# Circuit-Schematic.net
KiCad netlist of a schematic drawn in EAGLE
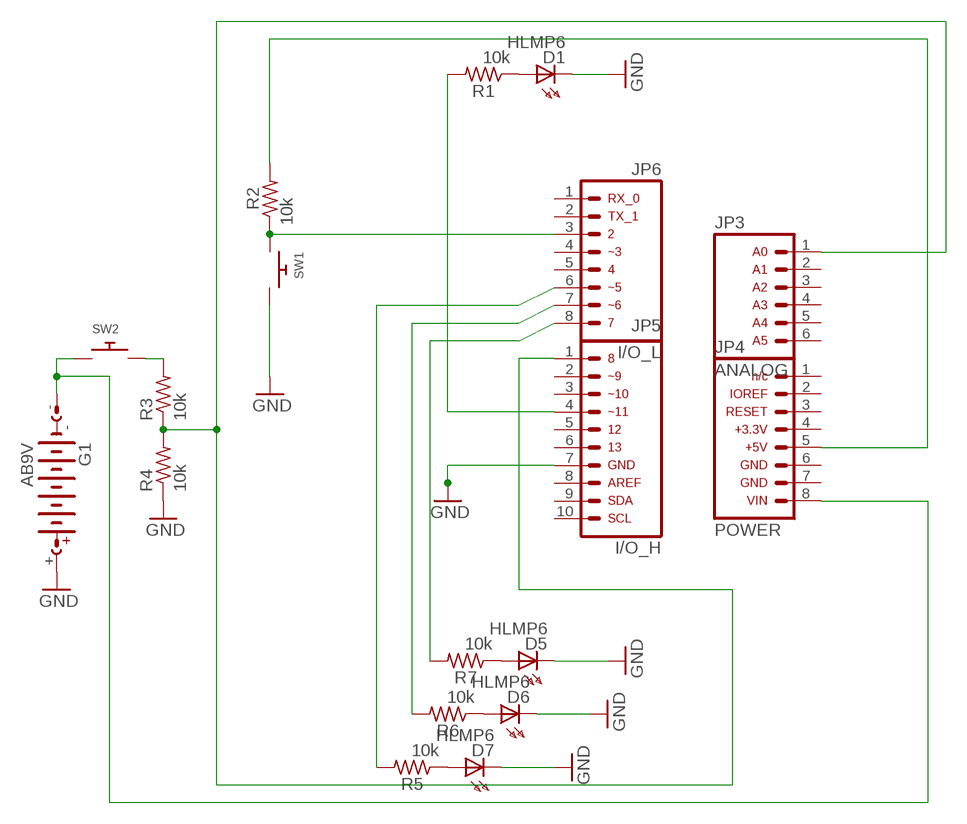
[diagram p0: schematic, sheet 1]

(export (version "E")
  (design (tool "Eeschema 10.0.6"))
  (components
    (comp (ref "D1")
      (value "HLMP6")
      (footprint "eagle-import:HLMP6")
      (fields (field (name "MF") "AGILENT TECHNOLOGIES") (field (name "MPN") "HLMP-6500"))
      (libsource (lib "eagle-import") (part "HLMP6"))
    )
    (comp (ref "D5")
      (value "HLMP6")
      (footprint "eagle-import:HLMP6")
      (fields (field (name "MF") "AGILENT TECHNOLOGIES") (field (name "MPN") "HLMP-6500"))
      (libsource (lib "eagle-import") (part "HLMP6"))
    )
    (comp (ref "D6")
      (value "HLMP6")
      (footprint "eagle-import:HLMP6")
      (fields (field (name "MF") "AGILENT TECHNOLOGIES") (field (name "MPN") "HLMP-6500"))
      (libsource (lib "eagle-import") (part "HLMP6"))
    )
    (comp (ref "D7")
      (value "HLMP6")
      (footprint "eagle-import:HLMP6")
      (fields (field (name "MF") "AGILENT TECHNOLOGIES") (field (name "MPN") "HLMP-6500"))
      (libsource (lib "eagle-import") (part "HLMP6"))
    )
    (comp (ref "G1")
      (value "AB9V")
      (footprint "eagle-import:AB9V")
      (libsource (lib "eagle-import") (part "AB9V"))
    )
    (comp (ref "JP3")
      (value "ARDUINO_CONN-ANALOGSIP")
      (footprint "eagle-import:CONN-1X06")
      (libsource (lib "eagle-import") (part "ARDUINO_CONN-ANALOGSIP"))
    )
    (comp (ref "JP4")
      (value "ARDUINO_CONN-POWERSIP")
      (footprint "eagle-import:CONN-1X08")
      (libsource (lib "eagle-import") (part "ARDUINO_CONN-POWERSIP"))
    )
    (comp (ref "JP5")
      (value "ARDUINO_CONN-IO_HSIP")
      (footprint "eagle-import:CONN-1X10")
      (libsource (lib "eagle-import") (part "ARDUINO_CONN-IO_HSIP"))
    )
    (comp (ref "JP6")
      (value "ARDUINO_CONN-IO_LSIP")
      (footprint "eagle-import:CONN-1X08")
      (libsource (lib "eagle-import") (part "ARDUINO_CONN-IO_LSIP"))
    )
    (comp (ref "R1")
      (value "10k")
      (footprint "eagle-import:R0805")
      (libsource (lib "eagle-import") (part "R-US_R0805"))
    )
    (comp (ref "R2")
      (value "10k")
      (footprint "eagle-import:R0805")
      (libsource (lib "eagle-import") (part "R-US_R0805"))
    )
    (comp (ref "R3")
      (value "10k")
      (footprint "eagle-import:R0805")
      (libsource (lib "eagle-import") (part "R-US_R0805"))
    )
    (comp (ref "R4")
      (value "10k")
      (footprint "eagle-import:R0805")
      (libsource (lib "eagle-import") (part "R-US_R0805"))
    )
    (comp (ref "R5")
      (value "10k")
      (footprint "eagle-import:R0805")
      (libsource (lib "eagle-import") (part "R-US_R0805"))
    )
    (comp (ref "R6")
      (value "10k")
      (footprint "eagle-import:R0805")
      (libsource (lib "eagle-import") (part "R-US_R0805"))
    )
    (comp (ref "R7")
      (value "10k")
      (footprint "eagle-import:R0805")
      (libsource (lib "eagle-import") (part "R-US_R0805"))
    )
    (comp (ref "SW1")
      (value "SWITCH_PUSHBUTTONSOFTTOUCHSMD_SJ")
      (footprint "eagle-import:PUSHBUTTON_SMD_SJ")
      (libsource (lib "eagle-import") (part "SWITCH_PUSHBUTTONSOFTTOUCHSMD_SJ"))
    )
    (comp (ref "SW2")
      (value "SWITCH_PUSHBUTTONSOFTTOUCHSMD_SJ")
      (footprint "eagle-import:PUSHBUTTON_SMD_SJ")
      (libsource (lib "eagle-import") (part "SWITCH_PUSHBUTTONSOFTTOUCHSMD_SJ"))
    )
  )
  (nets
    (net (code "1") (name "GND") (class "Default")
      (node (ref "D1") (pin "K") (pinfunction "K_K") (pintype "passive"))
      (node (ref "D5") (pin "K") (pinfunction "K_K") (pintype "passive"))
      (node (ref "D6") (pin "K") (pinfunction "K_K") (pintype "passive"))
      (node (ref "D7") (pin "K") (pinfunction "K_K") (pintype "passive"))
      (node (ref "G1") (pin "+") (pinfunction "+_+") (pintype "passive"))
      (node (ref "JP5") (pin "7") (pinfunction "7_7") (pintype "passive"))
      (node (ref "R4") (pin "1") (pinfunction "1_1") (pintype "passive"))
      (node (ref "SW1") (pin "P$2") (pinfunction "P$2_P$2") (pintype "passive"))
    )
    (net (code "2") (name "Net-(D1-PadA)") (class "Default")
      (node (ref "D1") (pin "A") (pinfunction "A_A") (pintype "passive"))
      (node (ref "R1") (pin "1") (pinfunction "1_1") (pintype "passive"))
    )
    (net (code "3") (name "Net-(D5-PadA)") (class "Default")
      (node (ref "D5") (pin "A") (pinfunction "A_A") (pintype "passive"))
      (node (ref "R7") (pin "1") (pinfunction "1_1") (pintype "passive"))
    )
    (net (code "4") (name "Net-(D6-PadA)") (class "Default")
      (node (ref "D6") (pin "A") (pinfunction "A_A") (pintype "passive"))
      (node (ref "R6") (pin "1") (pinfunction "1_1") (pintype "passive"))
    )
    (net (code "5") (name "Net-(D7-PadA)") (class "Default")
      (node (ref "D7") (pin "A") (pinfunction "A_A") (pintype "passive"))
      (node (ref "R5") (pin "1") (pinfunction "1_1") (pintype "passive"))
    )
    (net (code "6") (name "Net-(G1-Pad-)") (class "Default")
      (node (ref "G1") (pin "-") (pinfunction "-_-") (pintype "passive"))
      (node (ref "JP4") (pin "8") (pinfunction "8_8") (pintype "passive"))
      (node (ref "SW2") (pin "P$1") (pinfunction "P$1_P$1") (pintype "passive"))
    )
    (net (code "7") (name "Net-(JP3-Pad1)") (class "Default")
      (node (ref "JP3") (pin "1") (pinfunction "1_1") (pintype "passive"))
      (node (ref "JP5") (pin "1") (pinfunction "1_1") (pintype "passive"))
      (node (ref "R3") (pin "1") (pinfunction "1_1") (pintype "passive"))
      (node (ref "R4") (pin "2") (pinfunction "2_2") (pintype "passive"))
    )
    (net (code "8") (name "Net-(JP4-Pad5)") (class "Default")
      (node (ref "JP4") (pin "5") (pinfunction "5_5") (pintype "passive"))
      (node (ref "R2") (pin "2") (pinfunction "2_2") (pintype "passive"))
    )
    (net (code "9") (name "Net-(JP5-Pad4)") (class "Default")
      (node (ref "JP5") (pin "4") (pinfunction "4_4") (pintype "passive"))
      (node (ref "R1") (pin "2") (pinfunction "2_2") (pintype "passive"))
    )
    (net (code "10") (name "Net-(JP6-Pad3)") (class "Default")
      (node (ref "JP6") (pin "3") (pinfunction "3_3") (pintype "passive"))
      (node (ref "R2") (pin "1") (pinfunction "1_1") (pintype "passive"))
      (node (ref "SW1") (pin "P$1") (pinfunction "P$1_P$1") (pintype "passive"))
    )
    (net (code "11") (name "Net-(JP6-Pad6)") (class "Default")
      (node (ref "JP6") (pin "6") (pinfunction "6_6") (pintype "passive"))
      (node (ref "R5") (pin "2") (pinfunction "2_2") (pintype "passive"))
    )
    (net (code "12") (name "Net-(JP6-Pad7)") (class "Default")
      (node (ref "JP6") (pin "7") (pinfunction "7_7") (pintype "passive"))
      (node (ref "R6") (pin "2") (pinfunction "2_2") (pintype "passive"))
    )
    (net (code "13") (name "Net-(JP6-Pad8)") (class "Default")
      (node (ref "JP6") (pin "8") (pinfunction "8_8") (pintype "passive"))
      (node (ref "R7") (pin "2") (pinfunction "2_2") (pintype "passive"))
    )
    (net (code "14") (name "Net-(R3-Pad2)") (class "Default")
      (node (ref "R3") (pin "2") (pinfunction "2_2") (pintype "passive"))
      (node (ref "SW2") (pin "P$2") (pinfunction "P$2_P$2") (pintype "passive"))
    )
    (net (code "15") (name "unconnected-(JP3-Pad2)") (class "Default")
      (node (ref "JP3") (pin "2") (pinfunction "2_2") (pintype "passive"))
    )
    (net (code "16") (name "unconnected-(JP3-Pad3)") (class "Default")
      (node (ref "JP3") (pin "3") (pinfunction "3_3") (pintype "passive"))
    )
    (net (code "17") (name "unconnected-(JP3-Pad4)") (class "Default")
      (node (ref "JP3") (pin "4") (pinfunction "4_4") (pintype "passive"))
    )
    (net (code "18") (name "unconnected-(JP3-Pad5)") (class "Default")
      (node (ref "JP3") (pin "5") (pinfunction "5_5") (pintype "passive"))
    )
    (net (code "19") (name "unconnected-(JP3-Pad6)") (class "Default")
      (node (ref "JP3") (pin "6") (pinfunction "6_6") (pintype "passive"))
    )
    (net (code "20") (name "unconnected-(JP4-Pad1)") (class "Default")
      (node (ref "JP4") (pin "1") (pinfunction "1_1") (pintype "passive"))
    )
    (net (code "21") (name "unconnected-(JP4-Pad2)") (class "Default")
      (node (ref "JP4") (pin "2") (pinfunction "2_2") (pintype "passive"))
    )
    (net (code "22") (name "unconnected-(JP4-Pad3)") (class "Default")
      (node (ref "JP4") (pin "3") (pinfunction "3_3") (pintype "passive"))
    )
    (net (code "23") (name "unconnected-(JP4-Pad4)") (class "Default")
      (node (ref "JP4") (pin "4") (pinfunction "4_4") (pintype "passive"))
    )
    (net (code "24") (name "unconnected-(JP4-Pad6)") (class "Default")
      (node (ref "JP4") (pin "6") (pinfunction "6_6") (pintype "passive"))
    )
    (net (code "25") (name "unconnected-(JP4-Pad7)") (class "Default")
      (node (ref "JP4") (pin "7") (pinfunction "7_7") (pintype "passive"))
    )
    (net (code "26") (name "unconnected-(JP5-Pad2)") (class "Default")
      (node (ref "JP5") (pin "2") (pinfunction "2_2") (pintype "passive"))
    )
    (net (code "27") (name "unconnected-(JP5-Pad3)") (class "Default")
      (node (ref "JP5") (pin "3") (pinfunction "3_3") (pintype "passive"))
    )
    (net (code "28") (name "unconnected-(JP5-Pad5)") (class "Default")
      (node (ref "JP5") (pin "5") (pinfunction "5_5") (pintype "passive"))
    )
    (net (code "29") (name "unconnected-(JP5-Pad6)") (class "Default")
      (node (ref "JP5") (pin "6") (pinfunction "6_6") (pintype "passive"))
    )
    (net (code "30") (name "unconnected-(JP5-Pad8)") (class "Default")
      (node (ref "JP5") (pin "8") (pinfunction "8_8") (pintype "passive"))
    )
    (net (code "31") (name "unconnected-(JP5-Pad9)") (class "Default")
      (node (ref "JP5") (pin "9") (pinfunction "9_9") (pintype "passive"))
    )
    (net (code "32") (name "unconnected-(JP5-Pad10)") (class "Default")
      (node (ref "JP5") (pin "10") (pinfunction "10_10") (pintype "passive"))
    )
    (net (code "33") (name "unconnected-(JP6-Pad1)") (class "Default")
      (node (ref "JP6") (pin "1") (pinfunction "1_1") (pintype "passive"))
    )
    (net (code "34") (name "unconnected-(JP6-Pad2)") (class "Default")
      (node (ref "JP6") (pin "2") (pinfunction "2_2") (pintype "passive"))
    )
    (net (code "35") (name "unconnected-(JP6-Pad4)") (class "Default")
      (node (ref "JP6") (pin "4") (pinfunction "4_4") (pintype "passive"))
    )
    (net (code "36") (name "unconnected-(JP6-Pad5)") (class "Default")
      (node (ref "JP6") (pin "5") (pinfunction "5_5") (pintype "passive"))
    )
  )
)
